# hotswap.net
KiCad netlist of a schematic drawn in EAGLE
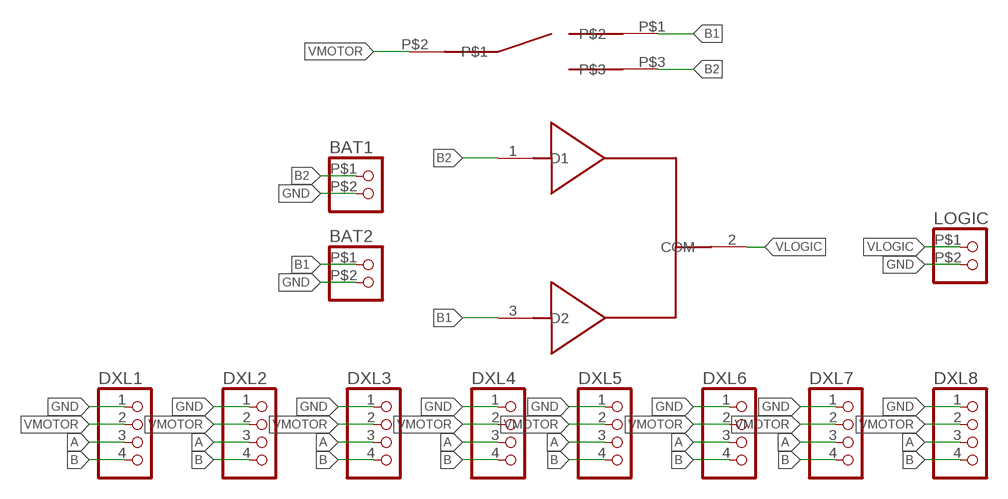
[diagram p0: schematic, sheet 1]

(export (version "E")
  (design (tool "Eeschema 10.0.6"))
  (components
    (comp (ref "BAT1")
      (value "CONNEC_1X02BIG")
      (footprint "eagle-import:CONNEC_1X02_BIG")
      (libsource (lib "eagle-import") (part "CONNEC_1X02BIG"))
    )
    (comp (ref "BAT2")
      (value "CONNEC_1X02BIG")
      (footprint "eagle-import:CONNEC_1X02_BIG")
      (libsource (lib "eagle-import") (part "CONNEC_1X02BIG"))
    )
    (comp (ref "DXL1")
      (value "CONNEC_1X04")
      (footprint "eagle-import:CONNEC_1X04")
      (libsource (lib "eagle-import") (part "CONNEC_1X04"))
    )
    (comp (ref "DXL2")
      (value "CONNEC_1X04")
      (footprint "eagle-import:CONNEC_1X04")
      (libsource (lib "eagle-import") (part "CONNEC_1X04"))
    )
    (comp (ref "DXL3")
      (value "CONNEC_1X04")
      (footprint "eagle-import:CONNEC_1X04")
      (libsource (lib "eagle-import") (part "CONNEC_1X04"))
    )
    (comp (ref "DXL4")
      (value "CONNEC_1X04")
      (footprint "eagle-import:CONNEC_1X04")
      (libsource (lib "eagle-import") (part "CONNEC_1X04"))
    )
    (comp (ref "DXL5")
      (value "CONNEC_1X04")
      (footprint "eagle-import:CONNEC_1X04")
      (libsource (lib "eagle-import") (part "CONNEC_1X04"))
    )
    (comp (ref "DXL6")
      (value "CONNEC_1X04")
      (footprint "eagle-import:CONNEC_1X04")
      (libsource (lib "eagle-import") (part "CONNEC_1X04"))
    )
    (comp (ref "DXL7")
      (value "CONNEC_1X04")
      (footprint "eagle-import:CONNEC_1X04")
      (libsource (lib "eagle-import") (part "CONNEC_1X04"))
    )
    (comp (ref "DXL8")
      (value "CONNEC_1X04")
      (footprint "eagle-import:CONNEC_1X04")
      (libsource (lib "eagle-import") (part "CONNEC_1X04"))
    )
    (comp (ref "LOGIC")
      (value "CONNEC_1X02BIG")
      (footprint "eagle-import:CONNEC_1X02_BIG")
      (libsource (lib "eagle-import") (part "CONNEC_1X02BIG"))
    )
    (comp (ref "U$1")
      (value "MBR1545CTG")
      (footprint "eagle-import:TO-220-ALT")
      (libsource (lib "eagle-import") (part "MBR1545CTG"))
    )
    (comp (ref "U$2")
      (value "BIG_SPDT")
      (footprint "eagle-import:BIG_SPDT")
      (libsource (lib "eagle-import") (part "BIG_SPDT"))
    )
  )
  (nets
    (net (code "1") (name "A") (class "Default")
      (node (ref "DXL1") (pin "3") (pinfunction "3_3") (pintype "passive"))
      (node (ref "DXL2") (pin "3") (pinfunction "3_3") (pintype "passive"))
      (node (ref "DXL3") (pin "3") (pinfunction "3_3") (pintype "passive"))
      (node (ref "DXL4") (pin "3") (pinfunction "3_3") (pintype "passive"))
      (node (ref "DXL5") (pin "3") (pinfunction "3_3") (pintype "passive"))
      (node (ref "DXL6") (pin "3") (pinfunction "3_3") (pintype "passive"))
      (node (ref "DXL7") (pin "3") (pinfunction "3_3") (pintype "passive"))
      (node (ref "DXL8") (pin "3") (pinfunction "3_3") (pintype "passive"))
    )
    (net (code "2") (name "B") (class "Default")
      (node (ref "DXL1") (pin "4") (pinfunction "4_4") (pintype "passive"))
      (node (ref "DXL2") (pin "4") (pinfunction "4_4") (pintype "passive"))
      (node (ref "DXL3") (pin "4") (pinfunction "4_4") (pintype "passive"))
      (node (ref "DXL4") (pin "4") (pinfunction "4_4") (pintype "passive"))
      (node (ref "DXL5") (pin "4") (pinfunction "4_4") (pintype "passive"))
      (node (ref "DXL6") (pin "4") (pinfunction "4_4") (pintype "passive"))
      (node (ref "DXL7") (pin "4") (pinfunction "4_4") (pintype "passive"))
      (node (ref "DXL8") (pin "4") (pinfunction "4_4") (pintype "passive"))
    )
    (net (code "3") (name "B1") (class "Default")
      (node (ref "BAT2") (pin "P$1") (pinfunction "1_P$1") (pintype "passive"))
      (node (ref "U$1") (pin "3") (pinfunction "D2_3") (pintype "bidirectional"))
      (node (ref "U$2") (pin "P$1") (pinfunction "P$2_P$1") (pintype "bidirectional"))
    )
    (net (code "4") (name "B2") (class "Default")
      (node (ref "BAT1") (pin "P$1") (pinfunction "1_P$1") (pintype "passive"))
      (node (ref "U$1") (pin "1") (pinfunction "D1_1") (pintype "bidirectional"))
      (node (ref "U$2") (pin "P$3") (pinfunction "P$3_P$3") (pintype "bidirectional"))
    )
    (net (code "5") (name "GND") (class "Default")
      (node (ref "BAT1") (pin "P$2") (pinfunction "2_P$2") (pintype "passive"))
      (node (ref "BAT2") (pin "P$2") (pinfunction "2_P$2") (pintype "passive"))
      (node (ref "DXL1") (pin "1") (pinfunction "1_1") (pintype "passive"))
      (node (ref "DXL2") (pin "1") (pinfunction "1_1") (pintype "passive"))
      (node (ref "DXL3") (pin "1") (pinfunction "1_1") (pintype "passive"))
      (node (ref "DXL4") (pin "1") (pinfunction "1_1") (pintype "passive"))
      (node (ref "DXL5") (pin "1") (pinfunction "1_1") (pintype "passive"))
      (node (ref "DXL6") (pin "1") (pinfunction "1_1") (pintype "passive"))
      (node (ref "DXL7") (pin "1") (pinfunction "1_1") (pintype "passive"))
      (node (ref "DXL8") (pin "1") (pinfunction "1_1") (pintype "passive"))
      (node (ref "LOGIC") (pin "P$2") (pinfunction "2_P$2") (pintype "passive"))
    )
    (net (code "6") (name "VLOGIC") (class "Default")
      (node (ref "LOGIC") (pin "P$1") (pinfunction "1_P$1") (pintype "passive"))
      (node (ref "U$1") (pin "2") (pinfunction "COM_2") (pintype "bidirectional"))
    )
    (net (code "7") (name "VMOTOR") (class "Default")
      (node (ref "DXL1") (pin "2") (pinfunction "2_2") (pintype "passive"))
      (node (ref "DXL2") (pin "2") (pinfunction "2_2") (pintype "passive"))
      (node (ref "DXL3") (pin "2") (pinfunction "2_2") (pintype "passive"))
      (node (ref "DXL4") (pin "2") (pinfunction "2_2") (pintype "passive"))
      (node (ref "DXL5") (pin "2") (pinfunction "2_2") (pintype "passive"))
      (node (ref "DXL6") (pin "2") (pinfunction "2_2") (pintype "passive"))
      (node (ref "DXL7") (pin "2") (pinfunction "2_2") (pintype "passive"))
      (node (ref "DXL8") (pin "2") (pinfunction "2_2") (pintype "passive"))
      (node (ref "U$2") (pin "P$2") (pinfunction "P$1_P$2") (pintype "bidirectional"))
    )
  )
)
